# pedala_axial_03.net
KiCad netlist of a schematic drawn in Altium Designer
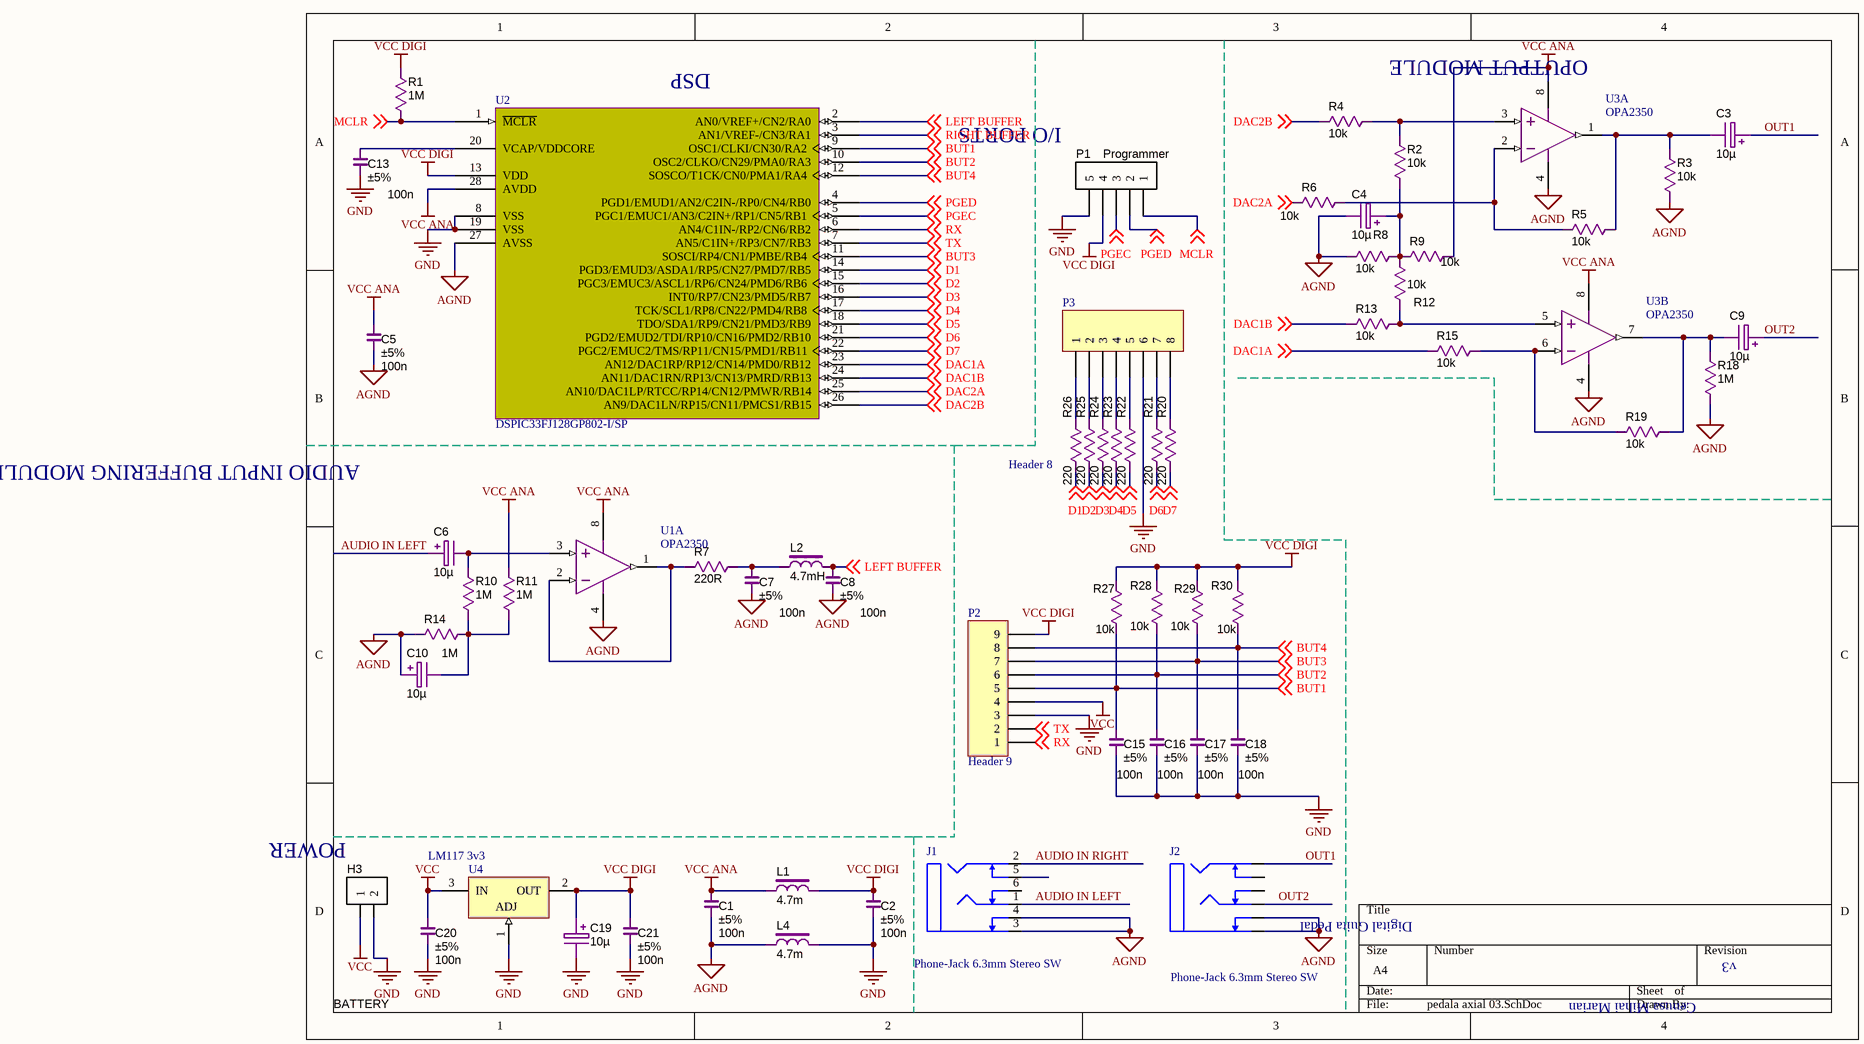
[diagram p0: pedala axial 03.SchDoc]

(export (version "E")
  (design (tool "Eeschema 10.0.6"))
  (components
    (comp (ref "C1")
      (value "100n")
      (footprint "Cap-Disk-D5.5-R2.54")
      (description "Capacitor SMD Cer 100nF 1206 NP0 50V 5%")
      (fields (field (name "TOLERANCE") "±5%"))
      (libsource (lib "pedala") (part "CAPC_100n_1206_NP0_50V_5%"))
    )
    (comp (ref "C2")
      (value "100n")
      (footprint "Cap-Disk-D5.5-R2.54")
      (description "Capacitor SMD Cer 100nF 1206 NP0 50V 5%")
      (fields (field (name "TOLERANCE") "±5%"))
      (libsource (lib "pedala") (part "CAPC_100n_1206_NP0_50V_5%"))
    )
    (comp (ref "C3")
      (value "10µ")
      (footprint "CAPAE250P680X1220_VERT")
      (description "Capacitor SMD Tant 330uF 20% 6V3 2917")
      (fields
        (field (name "TOLERANCE") "±20%")
        (field (name "MANUFACTURER PART NUMBER") "T520D337M006ATE015")
      )
      (libsource (lib "pedala") (part "CAPT_330u_2917_6V3"))
    )
    (comp (ref "C4")
      (value "10µ")
      (footprint "CAPAE250P680X1220_VERT")
      (description "Capacitor SMD Tant 330uF 20% 6V3 2917")
      (fields
        (field (name "TOLERANCE") "±20%")
        (field (name "MANUFACTURER PART NUMBER") "T520D337M006ATE015")
      )
      (libsource (lib "pedala") (part "CAPT_330u_2917_6V3"))
    )
    (comp (ref "C5")
      (value "100n")
      (footprint "Cap-Disk-D5.5-R2.54")
      (description "Capacitor SMD Cer 100nF 1206 NP0 50V 5%")
      (fields (field (name "TOLERANCE") "±5%"))
      (libsource (lib "pedala") (part "CAPC_100n_1206_NP0_50V_5%"))
    )
    (comp (ref "C6")
      (value "10µ")
      (footprint "CAPAE250P680X1220_VERT")
      (description "Capacitor SMD Tant 330uF 20% 6V3 2917")
      (fields
        (field (name "TOLERANCE") "±20%")
        (field (name "MANUFACTURER PART NUMBER") "T520D337M006ATE015")
      )
      (libsource (lib "pedala") (part "CAPT_330u_2917_6V3"))
    )
    (comp (ref "C7")
      (value "100n")
      (footprint "Cap-Disk-D5.5-R2.54")
      (description "Capacitor SMD Cer 100nF 1206 NP0 50V 5%")
      (fields (field (name "TOLERANCE") "±5%"))
      (libsource (lib "pedala") (part "CAPC_100n_1206_NP0_50V_5%"))
    )
    (comp (ref "C8")
      (value "100n")
      (footprint "Cap-Disk-D5.5-R2.54")
      (description "Capacitor SMD Cer 100nF 1206 NP0 50V 5%")
      (fields (field (name "TOLERANCE") "±5%"))
      (libsource (lib "pedala") (part "CAPC_100n_1206_NP0_50V_5%"))
    )
    (comp (ref "C9")
      (value "10µ")
      (footprint "CAPAE250P680X1220_VERT")
      (description "Capacitor SMD Tant 330uF 20% 6V3 2917")
      (fields
        (field (name "TOLERANCE") "±20%")
        (field (name "MANUFACTURER PART NUMBER") "T520D337M006ATE015")
      )
      (libsource (lib "pedala") (part "CAPT_330u_2917_6V3"))
    )
    (comp (ref "C10")
      (value "10µ")
      (footprint "CAPAE250P680X1220_VERT")
      (description "Capacitor SMD Tant 330uF 20% 6V3 2917")
      (fields
        (field (name "TOLERANCE") "±20%")
        (field (name "MANUFACTURER PART NUMBER") "T520D337M006ATE015")
      )
      (libsource (lib "pedala") (part "CAPT_330u_2917_6V3"))
    )
    (comp (ref "C13")
      (value "100n")
      (footprint "Cap-Disk-D5.5-R2.54")
      (description "Capacitor SMD Cer 100nF 1206 NP0 50V 5%")
      (fields (field (name "TOLERANCE") "±5%"))
      (libsource (lib "pedala") (part "CAPC_100n_1206_NP0_50V_5%"))
    )
    (comp (ref "C15")
      (value "100n")
      (footprint "Cap-Disk-D5.5-R2.54")
      (description "Capacitor SMD Cer 100nF 1206 NP0 50V 5%")
      (fields (field (name "TOLERANCE") "±5%"))
      (libsource (lib "pedala") (part "CAPC_100n_1206_NP0_50V_5%"))
    )
    (comp (ref "C16")
      (value "100n")
      (footprint "Cap-Disk-D5.5-R2.54")
      (description "Capacitor SMD Cer 100nF 1206 NP0 50V 5%")
      (fields (field (name "TOLERANCE") "±5%"))
      (libsource (lib "pedala") (part "CAPC_100n_1206_NP0_50V_5%"))
    )
    (comp (ref "C17")
      (value "100n")
      (footprint "Cap-Disk-D5.5-R2.54")
      (description "Capacitor SMD Cer 100nF 1206 NP0 50V 5%")
      (fields (field (name "TOLERANCE") "±5%"))
      (libsource (lib "pedala") (part "CAPC_100n_1206_NP0_50V_5%"))
    )
    (comp (ref "C18")
      (value "100n")
      (footprint "Cap-Disk-D5.5-R2.54")
      (description "Capacitor SMD Cer 100nF 1206 NP0 50V 5%")
      (fields (field (name "TOLERANCE") "±5%"))
      (libsource (lib "pedala") (part "CAPC_100n_1206_NP0_50V_5%"))
    )
    (comp (ref "C19")
      (value "10µ")
      (footprint "R1206-1%")
      (description "Capacitor SMD Tant 330uF 20% 6V3 2917")
      (fields
        (field (name "TOLERANCE") "±20%")
        (field (name "MANUFACTURER PART NUMBER") "T520D337M006ATE015")
      )
      (libsource (lib "pedala") (part "CAPT_330u_2917_6V3"))
    )
    (comp (ref "C20")
      (value "100n")
      (footprint "Cap-Disk-D5.5-R2.54")
      (description "Capacitor SMD Cer 100nF 1206 NP0 50V 5%")
      (fields (field (name "TOLERANCE") "±5%"))
      (libsource (lib "pedala") (part "CAPC_100n_1206_NP0_50V_5%"))
    )
    (comp (ref "C21")
      (value "100n")
      (footprint "Cap-Disk-D5.5-R2.54")
      (description "Capacitor SMD Cer 100nF 1206 NP0 50V 5%")
      (fields (field (name "TOLERANCE") "±5%"))
      (libsource (lib "pedala") (part "CAPC_100n_1206_NP0_50V_5%"))
    )
    (comp (ref "H3")
      (value "BATTERY")
      (footprint "HDR_1X2X276")
      (description "Header, 2-pin")
      (libsource (lib "pedala_2") (part "Header2P"))
    )
    (comp (ref "J1")
      (value "Phone-Jack 6.3mm Stereo SW")
      (footprint "Phone-Jack Stereo SW 6.3mm")
      (libsource (lib "Connektor") (part "Phone-Jack 6.3mm Stereo SW"))
    )
    (comp (ref "J2")
      (value "Phone-Jack 6.3mm Stereo SW")
      (footprint "Phone-Jack Stereo SW 6.3mm")
      (libsource (lib "") (part "Phone-Jack 6.3mm Stereo SW_1"))
    )
    (comp (ref "L1")
      (value "4.7m")
      (footprint "Dr-CW8A")
      (description "Power Inductor 180µH 10% SMD Toroid")
      (fields (field (name "TOLERANCE") "±10%") (field (name "Comment") "INDC_180u_Toroid"))
      (libsource (lib "pedala") (part "INDC_180u_Toroid"))
    )
    (comp (ref "L2")
      (value "4.7mH")
      (footprint "Dr-CW8A")
      (description "Power Inductor 180µH 10% SMD Toroid")
      (fields (field (name "TOLERANCE") "±10%") (field (name "Comment") "INDC_180u_Toroid"))
      (libsource (lib "pedala") (part "INDC_180u_Toroid"))
    )
    (comp (ref "L4")
      (value "4.7m")
      (footprint "Dr-CW8A")
      (description "Power Inductor 180µH 10% SMD Toroid")
      (fields (field (name "TOLERANCE") "±10%") (field (name "Comment") "INDC_180u_Toroid"))
      (libsource (lib "pedala") (part "INDC_180u_Toroid"))
    )
    (comp (ref "P1")
      (value "Programmer")
      (footprint "HDR1X5_2.54MMP")
      (description "Header 5-pin")
      (libsource (lib "PBL - Connectors") (part "Header5P"))
    )
    (comp (ref "P2")
      (value "Header 9")
      (footprint "HDR1X9")
      (description "Header, 9-Pin")
      (fields (field (name "PUBLISHER") "Altium Limited"))
      (libsource (lib "Miscellaneous Connectors") (part "Header 9"))
    )
    (comp (ref "P3")
      (value "Header 8")
      (footprint "HDR1X8")
      (description "Header, 8-Pin")
      (fields (field (name "PUBLISHER") "Altium Limited"))
      (libsource (lib "Miscellaneous Connectors") (part "Header 8"))
    )
    (comp (ref "R1")
      (value "1M")
      (footprint "R0.25-300")
      (description "Resistor SMD chip 1M Ohm 0.125W 5% 0805")
      (fields (field (name "TOLERANCE") "±5%") (field (name "Comment") "Thick Film"))
      (libsource (lib "pedala") (part "RES_1M_0805_5%"))
    )
    (comp (ref "R2")
      (value "10k")
      (footprint "R0.25-300")
      (description "Resistor SMD chip 1M Ohm 0.125W 5% 0805")
      (fields (field (name "TOLERANCE") "±5%") (field (name "Comment") "Thick Film"))
      (libsource (lib "pedala") (part "RES_1M_0805_5%"))
    )
    (comp (ref "R3")
      (value "10k")
      (footprint "R0.25-300")
      (description "Resistor SMD chip 1M Ohm 0.125W 5% 0805")
      (fields (field (name "TOLERANCE") "±5%") (field (name "Comment") "Thick Film"))
      (libsource (lib "pedala") (part "RES_1M_0805_5%"))
    )
    (comp (ref "R4")
      (value "10k")
      (footprint "R0.25-300")
      (description "Resistor SMD chip 1M Ohm 0.125W 5% 0805")
      (fields (field (name "TOLERANCE") "±5%") (field (name "Comment") "Thick Film"))
      (libsource (lib "pedala") (part "RES_1M_0805_5%"))
    )
    (comp (ref "R5")
      (value "10k")
      (footprint "R0.25-300")
      (description "Resistor SMD chip 1M Ohm 0.125W 5% 0805")
      (fields (field (name "TOLERANCE") "±5%") (field (name "Comment") "Thick Film"))
      (libsource (lib "pedala") (part "RES_1M_0805_5%"))
    )
    (comp (ref "R6")
      (value "10k")
      (footprint "R0.25-300")
      (description "Resistor SMD chip 1M Ohm 0.125W 5% 0805")
      (fields (field (name "TOLERANCE") "±5%") (field (name "Comment") "Thick Film"))
      (libsource (lib "pedala") (part "RES_1M_0805_5%"))
    )
    (comp (ref "R7")
      (value "220R")
      (footprint "R0.25-300")
      (description "Resistor SMD chip 1M Ohm 0.125W 5% 0805")
      (fields (field (name "TOLERANCE") "±5%") (field (name "Comment") "Thick Film"))
      (libsource (lib "pedala") (part "RES_1M_0805_5%"))
    )
    (comp (ref "R8")
      (value "10k")
      (footprint "R0.25-300")
      (description "Resistor SMD chip 1M Ohm 0.125W 5% 0805")
      (fields (field (name "TOLERANCE") "±5%") (field (name "Comment") "Thick Film"))
      (libsource (lib "pedala") (part "RES_1M_0805_5%"))
    )
    (comp (ref "R9")
      (value "10k")
      (footprint "R0.25-300")
      (description "Resistor SMD chip 1M Ohm 0.125W 5% 0805")
      (fields (field (name "TOLERANCE") "±5%") (field (name "Comment") "Thick Film"))
      (libsource (lib "pedala") (part "RES_1M_0805_5%"))
    )
    (comp (ref "R10")
      (value "1M")
      (footprint "R0.25-300")
      (description "Resistor SMD chip 1M Ohm 0.125W 5% 0805")
      (fields (field (name "TOLERANCE") "±5%") (field (name "Comment") "Thick Film"))
      (libsource (lib "pedala") (part "RES_1M_0805_5%"))
    )
    (comp (ref "R11")
      (value "1M")
      (footprint "R0.25-300")
      (description "Resistor SMD chip 1M Ohm 0.125W 5% 0805")
      (fields (field (name "TOLERANCE") "±5%") (field (name "Comment") "Thick Film"))
      (libsource (lib "pedala") (part "RES_1M_0805_5%"))
    )
    (comp (ref "R12")
      (value "10k")
      (footprint "R0.25-300")
      (description "Resistor SMD chip 1M Ohm 0.125W 5% 0805")
      (fields (field (name "TOLERANCE") "±5%") (field (name "Comment") "Thick Film"))
      (libsource (lib "pedala") (part "RES_1M_0805_5%"))
    )
    (comp (ref "R13")
      (value "10k")
      (footprint "R0.25-300")
      (description "Resistor SMD chip 1M Ohm 0.125W 5% 0805")
      (fields (field (name "TOLERANCE") "±5%") (field (name "Comment") "Thick Film"))
      (libsource (lib "pedala") (part "RES_1M_0805_5%"))
    )
    (comp (ref "R14")
      (value "1M")
      (footprint "R0.25-300")
      (description "Resistor SMD chip 1M Ohm 0.125W 5% 0805")
      (fields (field (name "TOLERANCE") "±5%") (field (name "Comment") "Thick Film"))
      (libsource (lib "pedala") (part "RES_1M_0805_5%"))
    )
    (comp (ref "R15")
      (value "10k")
      (footprint "R0.25-300")
      (description "Resistor SMD chip 1M Ohm 0.125W 5% 0805")
      (fields (field (name "TOLERANCE") "±5%") (field (name "Comment") "Thick Film"))
      (libsource (lib "pedala") (part "RES_1M_0805_5%"))
    )
    (comp (ref "R18")
      (value "1M")
      (footprint "R0.25-300")
      (description "Resistor SMD chip 1M Ohm 0.125W 5% 0805")
      (fields (field (name "TOLERANCE") "±5%") (field (name "Comment") "Thick Film"))
      (libsource (lib "pedala") (part "RES_1M_0805_5%"))
    )
    (comp (ref "R19")
      (value "10k")
      (footprint "R0.25-300")
      (description "Resistor SMD chip 1M Ohm 0.125W 5% 0805")
      (fields (field (name "TOLERANCE") "±5%") (field (name "Comment") "Thick Film"))
      (libsource (lib "pedala") (part "RES_1M_0805_5%"))
    )
    (comp (ref "R20")
      (value "220")
      (footprint "R0.25-300")
      (description "Resistor SMD chip 1M Ohm 0.125W 5% 0805")
      (fields (field (name "TOLERANCE") "±5%") (field (name "Comment") "Thick Film"))
      (libsource (lib "pedala") (part "RES_1M_0805_5%"))
    )
    (comp (ref "R21")
      (value "220")
      (footprint "R0.25-300")
      (description "Resistor SMD chip 1M Ohm 0.125W 5% 0805")
      (fields (field (name "TOLERANCE") "±5%") (field (name "Comment") "Thick Film"))
      (libsource (lib "pedala") (part "RES_1M_0805_5%"))
    )
    (comp (ref "R22")
      (value "220")
      (footprint "R0.25-300")
      (description "Resistor SMD chip 1M Ohm 0.125W 5% 0805")
      (fields (field (name "TOLERANCE") "±5%") (field (name "Comment") "Thick Film"))
      (libsource (lib "pedala") (part "RES_1M_0805_5%"))
    )
    (comp (ref "R23")
      (value "220")
      (footprint "R0.25-300")
      (description "Resistor SMD chip 1M Ohm 0.125W 5% 0805")
      (fields (field (name "TOLERANCE") "±5%") (field (name "Comment") "Thick Film"))
      (libsource (lib "pedala") (part "RES_1M_0805_5%"))
    )
    (comp (ref "R24")
      (value "220")
      (footprint "R0.25-300")
      (description "Resistor SMD chip 1M Ohm 0.125W 5% 0805")
      (fields (field (name "TOLERANCE") "±5%") (field (name "Comment") "Thick Film"))
      (libsource (lib "pedala") (part "RES_1M_0805_5%"))
    )
    (comp (ref "R25")
      (value "220")
      (footprint "R0.25-300")
      (description "Resistor SMD chip 1M Ohm 0.125W 5% 0805")
      (fields (field (name "TOLERANCE") "±5%") (field (name "Comment") "Thick Film"))
      (libsource (lib "pedala") (part "RES_1M_0805_5%"))
    )
    (comp (ref "R26")
      (value "220")
      (footprint "R0.25-300")
      (description "Resistor SMD chip 1M Ohm 0.125W 5% 0805")
      (fields (field (name "TOLERANCE") "±5%") (field (name "Comment") "Thick Film"))
      (libsource (lib "pedala") (part "RES_1M_0805_5%"))
    )
    (comp (ref "R27")
      (value "10k")
      (footprint "R0.25-300")
      (description "Resistor SMD chip 1M Ohm 0.125W 5% 0805")
      (fields (field (name "TOLERANCE") "±5%") (field (name "Comment") "Thick Film"))
      (libsource (lib "pedala") (part "RES_1M_0805_5%"))
    )
    (comp (ref "R28")
      (value "10k")
      (footprint "R0.25-300")
      (description "Resistor SMD chip 1M Ohm 0.125W 5% 0805")
      (fields (field (name "TOLERANCE") "±5%") (field (name "Comment") "Thick Film"))
      (libsource (lib "pedala") (part "RES_1M_0805_5%"))
    )
    (comp (ref "R29")
      (value "10k")
      (footprint "R0.25-300")
      (description "Resistor SMD chip 1M Ohm 0.125W 5% 0805")
      (fields (field (name "TOLERANCE") "±5%") (field (name "Comment") "Thick Film"))
      (libsource (lib "pedala") (part "RES_1M_0805_5%"))
    )
    (comp (ref "R30")
      (value "10k")
      (footprint "R0.25-300")
      (description "Resistor SMD chip 1M Ohm 0.125W 5% 0805")
      (fields (field (name "TOLERANCE") "±5%") (field (name "Comment") "Thick Film"))
      (libsource (lib "pedala") (part "RES_1M_0805_5%"))
    )
    (comp (ref "U1")
      (value "OPA2350")
      (footprint "DIL8-300a")
      (fields (field (name "MANUFACTURER") "Texas Instruments") (field (name "PARTNUMBER") "OPA2313ID"))
      (libsource (lib "pedala") (part "OPA2313ID"))
    )
    (comp (ref "U2")
      (value "DSPIC33FJ128GP802-I/SP")
      (footprint "DIP28-300")
      (fields (field (name "MANUFACTURER") "Microchip"))
      (libsource (lib "pedala") (part "DSPIC33FJ128GP802-I/SP"))
    )
    (comp (ref "U3")
      (value "OPA2350")
      (footprint "DIL8-300a")
      (fields (field (name "MANUFACTURER") "Texas Instruments") (field (name "PARTNUMBER") "OPA2313ID"))
      (libsource (lib "pedala") (part "OPA2313ID"))
    )
    (comp (ref "U4")
      (value "LM117 3v3")
      (footprint "TO220-RB-650")
      (fields (field (name "MANUFACTURER") "Texas Instruments") (field (name "PARTNUMBER") "TL317CLP"))
      (libsource (lib "TI Power Management Standard Voltage Regulator") (part "TL317CLP"))
    )
  )
  (nets
    (net (code "1") (name "/AUDIO IN LEFT") (class "Default")
      (node (ref "C6") (pin "1") (pintype "passive"))
      (node (ref "J1") (pin "1") (pinfunction "R_1") (pintype "passive"))
    )
    (net (code "2") (name "/AUDIO IN RIGHT") (class "Default")
      (node (ref "J1") (pin "2") (pinfunction "L_2") (pintype "passive"))
    )
    (net (code "3") (name "/OUT1") (class "Default")
      (node (ref "C3") (pin "1") (pintype "passive"))
      (node (ref "J2") (pin "2") (pinfunction "L_2") (pintype "passive"))
    )
    (net (code "4") (name "/OUT2") (class "Default")
      (node (ref "C9") (pin "1") (pintype "passive"))
      (node (ref "J2") (pin "1") (pinfunction "R_1") (pintype "passive"))
    )
    (net (code "5") (name "AGND") (class "Default")
      (node (ref "C1") (pin "1") (pinfunction "1_1") (pintype "passive"))
      (node (ref "C10") (pin "1") (pintype "passive"))
      (node (ref "C4") (pin "2") (pintype "passive"))
      (node (ref "C5") (pin "1") (pinfunction "1_1") (pintype "passive"))
      (node (ref "C7") (pin "1") (pinfunction "1_1") (pintype "passive"))
      (node (ref "C8") (pin "1") (pinfunction "1_1") (pintype "passive"))
      (node (ref "J1") (pin "3") (pinfunction "G_3") (pintype "passive"))
      (node (ref "J1") (pin "4") (pinfunction "Ga_4") (pintype "passive"))
      (node (ref "J2") (pin "3") (pinfunction "G_3") (pintype "passive"))
      (node (ref "J2") (pin "4") (pinfunction "Ga_4") (pintype "passive"))
      (node (ref "L4") (pin "1") (pinfunction "1_1") (pintype "passive"))
      (node (ref "R14") (pin "2") (pinfunction "2_2") (pintype "passive"))
      (node (ref "R18") (pin "2") (pinfunction "2_2") (pintype "passive"))
      (node (ref "R3") (pin "2") (pinfunction "2_2") (pintype "passive"))
      (node (ref "R8") (pin "2") (pinfunction "2_2") (pintype "passive"))
      (node (ref "U1") (pin "4") (pinfunction "V-_4") (pintype "power_in"))
      (node (ref "U2") (pin "27") (pinfunction "AVSS_27") (pintype "power_in"))
      (node (ref "U3") (pin "4") (pinfunction "V-_4") (pintype "power_in"))
    )
    (net (code "6") (name "BUT1") (class "Default")
      (node (ref "C15") (pin "2") (pinfunction "2_2") (pintype "passive"))
      (node (ref "P2") (pin "5") (pinfunction "5_5") (pintype "passive"))
      (node (ref "R27") (pin "1") (pinfunction "1_1") (pintype "passive"))
      (node (ref "U2") (pin "9") (pinfunction "OSC1/CLKI/CN30/RA2_9") (pintype "bidirectional"))
    )
    (net (code "7") (name "BUT2") (class "Default")
      (node (ref "C16") (pin "2") (pinfunction "2_2") (pintype "passive"))
      (node (ref "P2") (pin "6") (pinfunction "6_6") (pintype "passive"))
      (node (ref "R28") (pin "1") (pinfunction "1_1") (pintype "passive"))
      (node (ref "U2") (pin "10") (pinfunction "OSC2/CLKO/CN29/PMA0/RA3_10") (pintype "bidirectional"))
    )
    (net (code "8") (name "BUT3") (class "Default")
      (node (ref "C17") (pin "2") (pinfunction "2_2") (pintype "passive"))
      (node (ref "P2") (pin "7") (pinfunction "7_7") (pintype "passive"))
      (node (ref "R29") (pin "1") (pinfunction "1_1") (pintype "passive"))
      (node (ref "U2") (pin "11") (pinfunction "SOSCI/RP4/CN1/PMBE/RB4_11") (pintype "bidirectional"))
    )
    (net (code "9") (name "BUT4") (class "Default")
      (node (ref "C18") (pin "2") (pinfunction "2_2") (pintype "passive"))
      (node (ref "P2") (pin "8") (pinfunction "8_8") (pintype "passive"))
      (node (ref "R30") (pin "1") (pinfunction "1_1") (pintype "passive"))
      (node (ref "U2") (pin "12") (pinfunction "SOSCO/T1CK/CN0/PMA1/RA4_12") (pintype "bidirectional"))
    )
    (net (code "10") (name "D1") (class "Default")
      (node (ref "R26") (pin "1") (pinfunction "1_1") (pintype "passive"))
      (node (ref "U2") (pin "14") (pinfunction "PGD3/EMUD3/ASDA1/RP5/CN27/PMD7/RB5_14") (pintype "bidirectional"))
    )
    (net (code "11") (name "D2") (class "Default")
      (node (ref "R25") (pin "1") (pinfunction "1_1") (pintype "passive"))
      (node (ref "U2") (pin "15") (pinfunction "PGC3/EMUC3/ASCL1/RP6/CN24/PMD6/RB6_15") (pintype "bidirectional"))
    )
    (net (code "12") (name "D3") (class "Default")
      (node (ref "R24") (pin "1") (pinfunction "1_1") (pintype "passive"))
      (node (ref "U2") (pin "16") (pinfunction "INT0/RP7/CN23/PMD5/RB7_16") (pintype "bidirectional"))
    )
    (net (code "13") (name "D4") (class "Default")
      (node (ref "R23") (pin "1") (pinfunction "1_1") (pintype "passive"))
      (node (ref "U2") (pin "17") (pinfunction "TCK/SCL1/RP8/CN22/PMD4/RB8_17") (pintype "bidirectional"))
    )
    (net (code "14") (name "D5") (class "Default")
      (node (ref "R22") (pin "1") (pinfunction "1_1") (pintype "passive"))
      (node (ref "U2") (pin "18") (pinfunction "TDO/SDA1/RP9/CN21/PMD3/RB9_18") (pintype "bidirectional"))
    )
    (net (code "15") (name "D6") (class "Default")
      (node (ref "R21") (pin "1") (pinfunction "1_1") (pintype "passive"))
      (node (ref "U2") (pin "21") (pinfunction "PGD2/EMUD2/TDI/RP10/CN16/PMD2/RB10_21") (pintype "bidirectional"))
    )
    (net (code "16") (name "D7") (class "Default")
      (node (ref "R20") (pin "1") (pinfunction "1_1") (pintype "passive"))
      (node (ref "U2") (pin "22") (pinfunction "PGC2/EMUC2/TMS/RP11/CN15/PMD1/RB11_22") (pintype "bidirectional"))
    )
    (net (code "17") (name "DAC1A") (class "Default")
      (node (ref "R15") (pin "1") (pinfunction "1_1") (pintype "passive"))
      (node (ref "U2") (pin "23") (pinfunction "AN12/DAC1RP/RP12/CN14/PMD0/RB12_23") (pintype "bidirectional"))
    )
    (net (code "18") (name "DAC1B") (class "Default")
      (node (ref "R13") (pin "1") (pinfunction "1_1") (pintype "passive"))
      (node (ref "U2") (pin "24") (pinfunction "AN11/DAC1RN/RP13/CN13/PMRD/RB13_24") (pintype "bidirectional"))
    )
    (net (code "19") (name "DAC2A") (class "Default")
      (node (ref "R6") (pin "2") (pinfunction "2_2") (pintype "passive"))
      (node (ref "U2") (pin "25") (pinfunction "AN10/DAC1LP/RTCC/RP14/CN12/PMWR/RB14_25") (pintype "bidirectional"))
    )
    (net (code "20") (name "DAC2B") (class "Default")
      (node (ref "R4") (pin "2") (pinfunction "2_2") (pintype "passive"))
      (node (ref "U2") (pin "26") (pinfunction "AN9/DAC1LN/RP15/CN11/PMCS1/RB15_26") (pintype "bidirectional"))
    )
    (net (code "21") (name "GND") (class "Default")
      (node (ref "C13") (pin "1") (pinfunction "1_1") (pintype "passive"))
      (node (ref "C15") (pin "1") (pinfunction "1_1") (pintype "passive"))
      (node (ref "C16") (pin "1") (pinfunction "1_1") (pintype "passive"))
      (node (ref "C17") (pin "1") (pinfunction "1_1") (pintype "passive"))
      (node (ref "C18") (pin "1") (pinfunction "1_1") (pintype "passive"))
      (node (ref "C19") (pin "2") (pintype "passive"))
      (node (ref "C2") (pin "1") (pinfunction "1_1") (pintype "passive"))
      (node (ref "C20") (pin "1") (pinfunction "1_1") (pintype "passive"))
      (node (ref "C21") (pin "1") (pinfunction "1_1") (pintype "passive"))
      (node (ref "H3") (pin "2") (pinfunction "2_2") (pintype "passive"))
      (node (ref "L4") (pin "2") (pinfunction "2_2") (pintype "passive"))
      (node (ref "P1") (pin "5") (pinfunction "5_5") (pintype "passive"))
      (node (ref "P2") (pin "3") (pinfunction "3_3") (pintype "passive"))
      (node (ref "P3") (pin "6") (pinfunction "6_6") (pintype "passive"))
      (node (ref "U2") (pin "19") (pinfunction "VSS_19") (pintype "power_in"))
      (node (ref "U2") (pin "8") (pinfunction "VSS_8") (pintype "power_in"))
      (node (ref "U4") (pin "1") (pinfunction "GND_1") (pintype "input"))
    )
    (net (code "22") (name "LEFT BUFFER") (class "Default")
      (node (ref "C8") (pin "2") (pinfunction "2_2") (pintype "passive"))
      (node (ref "L2") (pin "2") (pinfunction "2_2") (pintype "passive"))
      (node (ref "U2") (pin "2") (pinfunction "AN0/VREF+/CN2/RA0_2") (pintype "bidirectional"))
    )
    (net (code "23") (name "MCLR") (class "Default")
      (node (ref "P1") (pin "1") (pinfunction "1_1") (pintype "passive"))
      (node (ref "R1") (pin "1") (pinfunction "1_1") (pintype "passive"))
      (node (ref "U2") (pin "1") (pinfunction "~{MCLR}_1") (pintype "input"))
    )
    (net (code "24") (name "Net-(C4-Pad1)") (class "Default")
      (node (ref "C4") (pin "1") (pintype "passive"))
      (node (ref "R12") (pin "1") (pinfunction "1_1") (pintype "passive"))
      (node (ref "R2") (pin "1") (pinfunction "1_1") (pintype "passive"))
      (node (ref "R8") (pin "1") (pinfunction "1_1") (pintype "passive"))
      (node (ref "R9") (pin "2") (pinfunction "2_2") (pintype "passive"))
    )
    (net (code "25") (name "Net-(C7-Pad2)") (class "Default")
      (node (ref "C7") (pin "2") (pinfunction "2_2") (pintype "passive"))
      (node (ref "L2") (pin "1") (pinfunction "1_1") (pintype "passive"))
      (node (ref "R7") (pin "2") (pinfunction "2_2") (pintype "passive"))
    )
    (net (code "26") (name "Net-(C10-Pad2)") (class "Default")
      (node (ref "C10") (pin "2") (pintype "passive"))
      (node (ref "R10") (pin "2") (pinfunction "2_2") (pintype "passive"))
      (node (ref "R11") (pin "2") (pinfunction "2_2") (pintype "passive"))
      (node (ref "R14") (pin "1") (pinfunction "1_1") (pintype "passive"))
    )
    (net (code "27") (name "Net-(P3-Pad1)") (class "Default")
      (node (ref "P3") (pin "1") (pinfunction "1_1") (pintype "passive"))
      (node (ref "R26") (pin "2") (pinfunction "2_2") (pintype "passive"))
    )
    (net (code "28") (name "Net-(P3-Pad2)") (class "Default")
      (node (ref "P3") (pin "2") (pinfunction "2_2") (pintype "passive"))
      (node (ref "R25") (pin "2") (pinfunction "2_2") (pintype "passive"))
    )
    (net (code "29") (name "Net-(P3-Pad3)") (class "Default")
      (node (ref "P3") (pin "3") (pinfunction "3_3") (pintype "passive"))
      (node (ref "R24") (pin "2") (pinfunction "2_2") (pintype "passive"))
    )
    (net (code "30") (name "Net-(P3-Pad4)") (class "Default")
      (node (ref "P3") (pin "4") (pinfunction "4_4") (pintype "passive"))
      (node (ref "R23") (pin "2") (pinfunction "2_2") (pintype "passive"))
    )
    (net (code "31") (name "Net-(P3-Pad5)") (class "Default")
      (node (ref "P3") (pin "5") (pinfunction "5_5") (pintype "passive"))
      (node (ref "R22") (pin "2") (pinfunction "2_2") (pintype "passive"))
    )
    (net (code "32") (name "Net-(P3-Pad7)") (class "Default")
      (node (ref "P3") (pin "7") (pinfunction "7_7") (pintype "passive"))
      (node (ref "R21") (pin "2") (pinfunction "2_2") (pintype "passive"))
    )
    (net (code "33") (name "Net-(P3-Pad8)") (class "Default")
      (node (ref "P3") (pin "8") (pinfunction "8_8") (pintype "passive"))
      (node (ref "R20") (pin "2") (pinfunction "2_2") (pintype "passive"))
    )
    (net (code "34") (name "Net-(U1A-IN_A+)") (class "Default")
      (node (ref "C6") (pin "2") (pintype "passive"))
      (node (ref "R10") (pin "1") (pinfunction "1_1") (pintype "passive"))
      (node (ref "U1") (pin "3") (pinfunction "IN_A+_3") (pintype "input"))
    )
    (net (code "35") (name "Net-(U1A-IN_A-)") (class "Default")
      (node (ref "R7") (pin "1") (pinfunction "1_1") (pintype "passive"))
      (node (ref "U1") (pin "1") (pinfunction "OUT_A_1") (pintype "output"))
      (node (ref "U1") (pin "2") (pinfunction "IN_A-_2") (pintype "input"))
    )
    (net (code "36") (name "Net-(U2-VCAP{slash}VDDCORE)") (class "Default")
      (node (ref "C13") (pin "2") (pinfunction "2_2") (pintype "passive"))
      (node (ref "U2") (pin "20") (pinfunction "VCAP/VDDCORE_20") (pintype "power_in"))
    )
    (net (code "37") (name "Net-(U3A-IN_A+)") (class "Default")
      (node (ref "R2") (pin "2") (pinfunction "2_2") (pintype "passive"))
      (node (ref "R4") (pin "1") (pinfunction "1_1") (pintype "passive"))
      (node (ref "U3") (pin "3") (pinfunction "IN_A+_3") (pintype "input"))
    )
    (net (code "38") (name "Net-(U3A-IN_A-)") (class "Default")
      (node (ref "R5") (pin "2") (pinfunction "2_2") (pintype "passive"))
      (node (ref "R6") (pin "1") (pinfunction "1_1") (pintype "passive"))
      (node (ref "U3") (pin "2") (pinfunction "IN_A-_2") (pintype "input"))
    )
    (net (code "39") (name "Net-(U3A-OUT_A)") (class "Default")
      (node (ref "C3") (pin "2") (pintype "passive"))
      (node (ref "R3") (pin "1") (pinfunction "1_1") (pintype "passive"))
      (node (ref "R5") (pin "1") (pinfunction "1_1") (pintype "passive"))
      (node (ref "U3") (pin "1") (pinfunction "OUT_A_1") (pintype "output"))
    )
    (net (code "40") (name "Net-(U3B-IN_B+)") (class "Default")
      (node (ref "R12") (pin "2") (pinfunction "2_2") (pintype "passive"))
      (node (ref "R13") (pin "2") (pinfunction "2_2") (pintype "passive"))
      (node (ref "U3") (pin "5") (pinfunction "IN_B+_5") (pintype "input"))
    )
    (net (code "41") (name "Net-(U3B-IN_B-)") (class "Default")
      (node (ref "R15") (pin "2") (pinfunction "2_2") (pintype "passive"))
      (node (ref "R19") (pin "2") (pinfunction "2_2") (pintype "passive"))
      (node (ref "U3") (pin "6") (pinfunction "IN_B-_6") (pintype "input"))
    )
    (net (code "42") (name "Net-(U3B-OUT_B)") (class "Default")
      (node (ref "C9") (pin "2") (pintype "passive"))
      (node (ref "R18") (pin "1") (pinfunction "1_1") (pintype "passive"))
      (node (ref "R19") (pin "1") (pinfunction "1_1") (pintype "passive"))
      (node (ref "U3") (pin "7") (pinfunction "OUT_B_7") (pintype "output"))
    )
    (net (code "43") (name "PGEC") (class "Default")
      (node (ref "P1") (pin "3") (pinfunction "3_3") (pintype "passive"))
      (node (ref "U2") (pin "5") (pinfunction "PGC1/EMUC1/AN3/C2IN+/RP1/CN5/RB1_5") (pintype "bidirectional"))
    )
    (net (code "44") (name "PGED") (class "Default")
      (node (ref "P1") (pin "2") (pinfunction "2_2") (pintype "passive"))
      (node (ref "U2") (pin "4") (pinfunction "PGD1/EMUD1/AN2/C2IN-/RP0/CN4/RB0_4") (pintype "bidirectional"))
    )
    (net (code "45") (name "RIGHT BUFFER") (class "Default")
      (node (ref "U2") (pin "3") (pinfunction "AN1/VREF-/CN3/RA1_3") (pintype "bidirectional"))
    )
    (net (code "46") (name "RX") (class "Default")
      (node (ref "P2") (pin "1") (pinfunction "1_1") (pintype "passive"))
      (node (ref "U2") (pin "6") (pinfunction "AN4/C1IN-/RP2/CN6/RB2_6") (pintype "bidirectional"))
    )
    (net (code "47") (name "TX") (class "Default")
      (node (ref "P2") (pin "2") (pinfunction "2_2") (pintype "passive"))
      (node (ref "U2") (pin "7") (pinfunction "AN5/C1IN+/RP3/CN7/RB3_7") (pintype "bidirectional"))
    )
    (net (code "48") (name "VCC") (class "Default")
      (node (ref "C20") (pin "2") (pinfunction "2_2") (pintype "passive"))
      (node (ref "H3") (pin "1") (pinfunction "1_1") (pintype "passive"))
      (node (ref "P2") (pin "4") (pinfunction "4_4") (pintype "passive"))
      (node (ref "U4") (pin "3") (pinfunction "IN_3") (pintype "power_in"))
    )
    (net (code "49") (name "VCC ANA") (class "Default")
      (node (ref "C1") (pin "2") (pinfunction "2_2") (pintype "passive"))
      (node (ref "C5") (pin "2") (pinfunction "2_2") (pintype "passive"))
      (node (ref "L1") (pin "1") (pinfunction "1_1") (pintype "passive"))
      (node (ref "R11") (pin "1") (pinfunction "1_1") (pintype "passive"))
      (node (ref "R9") (pin "1") (pinfunction "1_1") (pintype "passive"))
      (node (ref "U1") (pin "8") (pinfunction "V+_8") (pintype "power_in"))
      (node (ref "U2") (pin "28") (pinfunction "AVDD_28") (pintype "power_in"))
      (node (ref "U3") (pin "8") (pinfunction "V+_8") (pintype "power_in"))
    )
    (net (code "50") (name "VCC DIGI") (class "Default")
      (node (ref "C19") (pin "1") (pintype "passive"))
      (node (ref "C2") (pin "2") (pinfunction "2_2") (pintype "passive"))
      (node (ref "C21") (pin "2") (pinfunction "2_2") (pintype "passive"))
      (node (ref "L1") (pin "2") (pinfunction "2_2") (pintype "passive"))
      (node (ref "P1") (pin "4") (pinfunction "4_4") (pintype "passive"))
      (node (ref "P2") (pin "9") (pinfunction "9_9") (pintype "passive"))
      (node (ref "R1") (pin "2") (pinfunction "2_2") (pintype "passive"))
      (node (ref "R27") (pin "2") (pinfunction "2_2") (pintype "passive"))
      (node (ref "R28") (pin "2") (pinfunction "2_2") (pintype "passive"))
      (node (ref "R29") (pin "2") (pinfunction "2_2") (pintype "passive"))
      (node (ref "R30") (pin "2") (pinfunction "2_2") (pintype "passive"))
      (node (ref "U2") (pin "13") (pinfunction "VDD_13") (pintype "power_in"))
      (node (ref "U4") (pin "2") (pinfunction "OUT_2") (pintype "power_in"))
    )
    (net (code "51") (name "unconnected-(J1-La-Pad5)") (class "Default")
      (node (ref "J1") (pin "5") (pinfunction "La_5") (pintype "passive"))
    )
    (net (code "52") (name "unconnected-(J1-Ra-Pad6)") (class "Default")
      (node (ref "J1") (pin "6") (pinfunction "Ra_6") (pintype "passive"))
    )
    (net (code "53") (name "unconnected-(J2-La-Pad5)") (class "Default")
      (node (ref "J2") (pin "5") (pinfunction "La_5") (pintype "passive"))
    )
    (net (code "54") (name "unconnected-(J2-Ra-Pad6)") (class "Default")
      (node (ref "J2") (pin "6") (pinfunction "Ra_6") (pintype "passive"))
    )
  )
)
